# HeaderB.net
KiCad netlist of a schematic drawn in Altium Designer
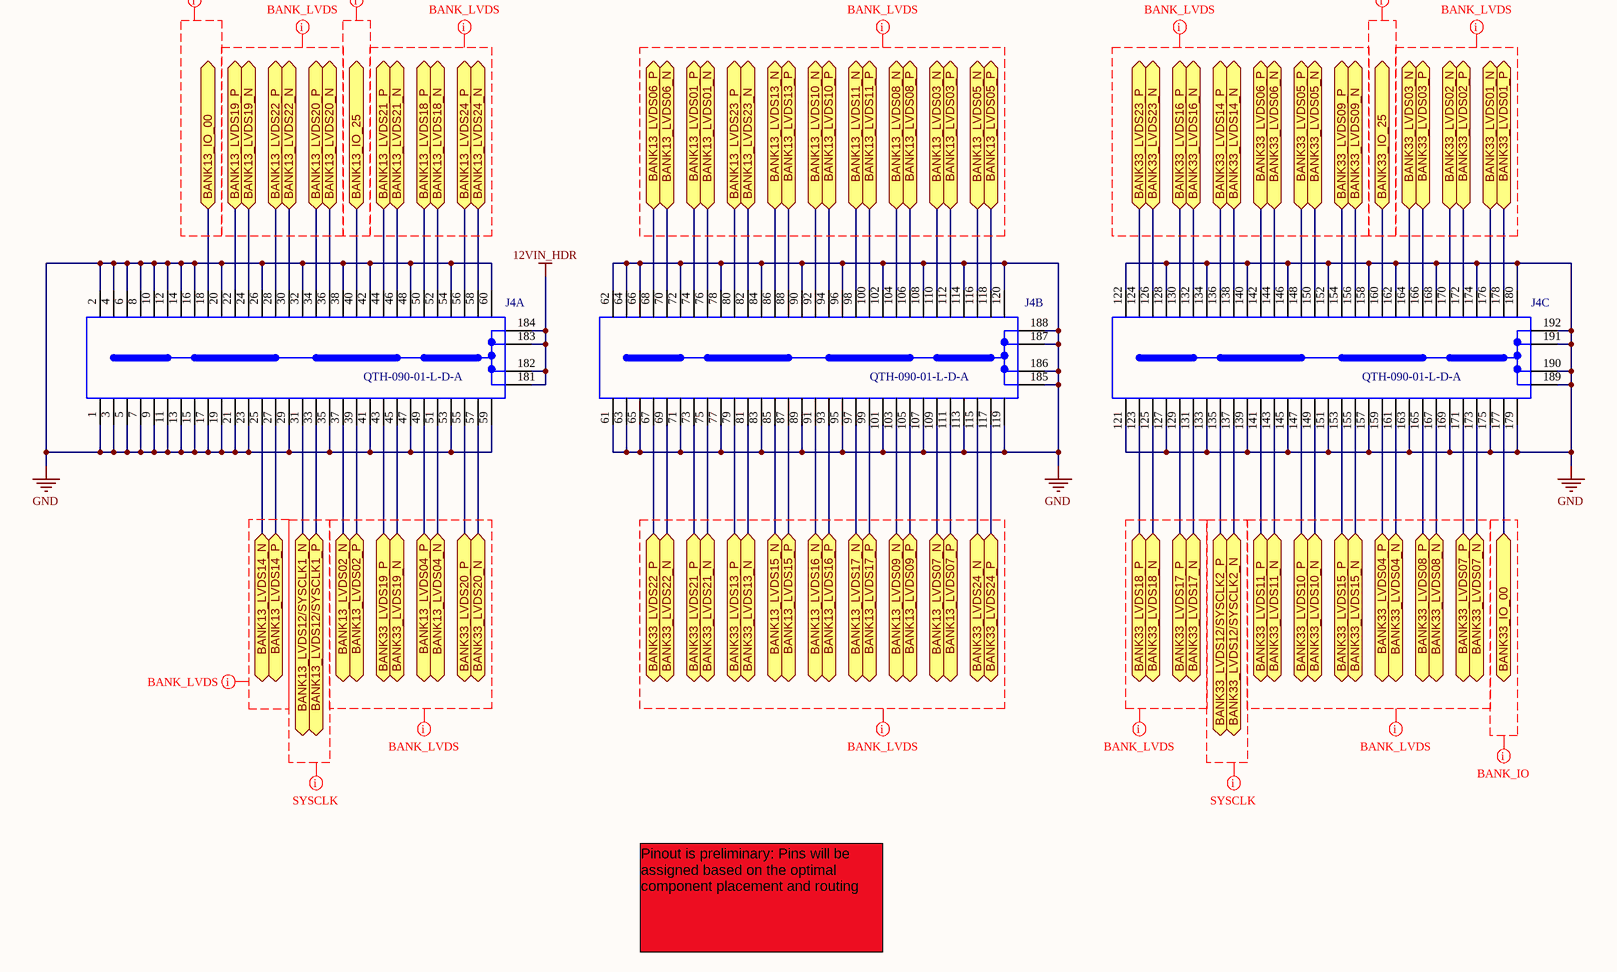
[diagram p0: HeaderB.SchDoc]

(export (version "E")
  (design (tool "Eeschema 10.0.6"))
  (components
    (comp (ref "J4")
      (value "QTH-090-01-L-D-A")
      (footprint "QTH-090-01-L-D-A")
      (description "Connector Header HS .5mm 180 pin DL AU")
      (libsource (lib "parts") (part "QTH-090-01-L-D-A"))
    )
  )
  (nets
    (net (code "1") (name "/BANK13_IO_00") (class "Default")
      (node (ref "J4") (pin "18") (pinfunction "18_18") (pintype "passive"))
    )
    (net (code "2") (name "/BANK13_IO_25") (class "Default")
      (node (ref "J4") (pin "40") (pinfunction "40_40") (pintype "passive"))
    )
    (net (code "3") (name "/BANK13_LVDS01_N") (class "Default")
      (node (ref "J4") (pin "76") (pinfunction "76_76") (pintype "passive"))
    )
    (net (code "4") (name "/BANK13_LVDS01_P") (class "Default")
      (node (ref "J4") (pin "74") (pinfunction "74_74") (pintype "passive"))
    )
    (net (code "5") (name "/BANK13_LVDS02_N") (class "Default")
      (node (ref "J4") (pin "37") (pinfunction "37_37") (pintype "passive"))
    )
    (net (code "6") (name "/BANK13_LVDS02_P") (class "Default")
      (node (ref "J4") (pin "39") (pinfunction "39_39") (pintype "passive"))
    )
    (net (code "7") (name "/BANK13_LVDS03_N") (class "Default")
      (node (ref "J4") (pin "110") (pinfunction "110_110") (pintype "passive"))
    )
    (net (code "8") (name "/BANK13_LVDS03_P") (class "Default")
      (node (ref "J4") (pin "112") (pinfunction "112_112") (pintype "passive"))
    )
    (net (code "9") (name "/BANK13_LVDS04_N") (class "Default")
      (node (ref "J4") (pin "51") (pinfunction "51_51") (pintype "passive"))
    )
    (net (code "10") (name "/BANK13_LVDS04_P") (class "Default")
      (node (ref "J4") (pin "49") (pinfunction "49_49") (pintype "passive"))
    )
    (net (code "11") (name "/BANK13_LVDS05_N") (class "Default")
      (node (ref "J4") (pin "116") (pinfunction "116_116") (pintype "passive"))
    )
    (net (code "12") (name "/BANK13_LVDS05_P") (class "Default")
      (node (ref "J4") (pin "118") (pinfunction "118_118") (pintype "passive"))
    )
    (net (code "13") (name "/BANK13_LVDS06_N") (class "Default")
      (node (ref "J4") (pin "70") (pinfunction "70_70") (pintype "passive"))
    )
    (net (code "14") (name "/BANK13_LVDS06_P") (class "Default")
      (node (ref "J4") (pin "68") (pinfunction "68_68") (pintype "passive"))
    )
    (net (code "15") (name "/BANK13_LVDS07_N") (class "Default")
      (node (ref "J4") (pin "109") (pinfunction "109_109") (pintype "passive"))
    )
    (net (code "16") (name "/BANK13_LVDS07_P") (class "Default")
      (node (ref "J4") (pin "111") (pinfunction "111_111") (pintype "passive"))
    )
    (net (code "17") (name "/BANK13_LVDS08_N") (class "Default")
      (node (ref "J4") (pin "104") (pinfunction "104_104") (pintype "passive"))
    )
    (net (code "18") (name "/BANK13_LVDS08_P") (class "Default")
      (node (ref "J4") (pin "106") (pinfunction "106_106") (pintype "passive"))
    )
    (net (code "19") (name "/BANK13_LVDS09_N") (class "Default")
      (node (ref "J4") (pin "103") (pinfunction "103_103") (pintype "passive"))
    )
    (net (code "20") (name "/BANK13_LVDS09_P") (class "Default")
      (node (ref "J4") (pin "105") (pinfunction "105_105") (pintype "passive"))
    )
    (net (code "21") (name "/BANK13_LVDS10_N") (class "Default")
      (node (ref "J4") (pin "92") (pinfunction "92_92") (pintype "passive"))
    )
    (net (code "22") (name "/BANK13_LVDS10_P") (class "Default")
      (node (ref "J4") (pin "94") (pinfunction "94_94") (pintype "passive"))
    )
    (net (code "23") (name "/BANK13_LVDS11_N") (class "Default")
      (node (ref "J4") (pin "98") (pinfunction "98_98") (pintype "passive"))
    )
    (net (code "24") (name "/BANK13_LVDS11_P") (class "Default")
      (node (ref "J4") (pin "100") (pinfunction "100_100") (pintype "passive"))
    )
    (net (code "25") (name "/BANK13_LVDS12{slash}SYSCLK1_N") (class "Default")
      (node (ref "J4") (pin "31") (pinfunction "31_31") (pintype "passive"))
    )
    (net (code "26") (name "/BANK13_LVDS12{slash}SYSCLK1_P") (class "Default")
      (node (ref "J4") (pin "33") (pinfunction "33_33") (pintype "passive"))
    )
    (net (code "27") (name "/BANK13_LVDS13_N") (class "Default")
      (node (ref "J4") (pin "86") (pinfunction "86_86") (pintype "passive"))
    )
    (net (code "28") (name "/BANK13_LVDS13_P") (class "Default")
      (node (ref "J4") (pin "88") (pinfunction "88_88") (pintype "passive"))
    )
    (net (code "29") (name "/BANK13_LVDS14_N") (class "Default")
      (node (ref "J4") (pin "25") (pinfunction "25_25") (pintype "passive"))
    )
    (net (code "30") (name "/BANK13_LVDS14_P") (class "Default")
      (node (ref "J4") (pin "27") (pinfunction "27_27") (pintype "passive"))
    )
    (net (code "31") (name "/BANK13_LVDS15_N") (class "Default")
      (node (ref "J4") (pin "85") (pinfunction "85_85") (pintype "passive"))
    )
    (net (code "32") (name "/BANK13_LVDS15_P") (class "Default")
      (node (ref "J4") (pin "87") (pinfunction "87_87") (pintype "passive"))
    )
    (net (code "33") (name "/BANK13_LVDS16_N") (class "Default")
      (node (ref "J4") (pin "91") (pinfunction "91_91") (pintype "passive"))
    )
    (net (code "34") (name "/BANK13_LVDS16_P") (class "Default")
      (node (ref "J4") (pin "93") (pinfunction "93_93") (pintype "passive"))
    )
    (net (code "35") (name "/BANK13_LVDS17_N") (class "Default")
      (node (ref "J4") (pin "97") (pinfunction "97_97") (pintype "passive"))
    )
    (net (code "36") (name "/BANK13_LVDS17_P") (class "Default")
      (node (ref "J4") (pin "99") (pinfunction "99_99") (pintype "passive"))
    )
    (net (code "37") (name "/BANK13_LVDS18_N") (class "Default")
      (node (ref "J4") (pin "52") (pinfunction "52_52") (pintype "passive"))
    )
    (net (code "38") (name "/BANK13_LVDS18_P") (class "Default")
      (node (ref "J4") (pin "50") (pinfunction "50_50") (pintype "passive"))
    )
    (net (code "39") (name "/BANK13_LVDS19_N") (class "Default")
      (node (ref "J4") (pin "24") (pinfunction "24_24") (pintype "passive"))
    )
    (net (code "40") (name "/BANK13_LVDS19_P") (class "Default")
      (node (ref "J4") (pin "22") (pinfunction "22_22") (pintype "passive"))
    )
    (net (code "41") (name "/BANK13_LVDS20_N") (class "Default")
      (node (ref "J4") (pin "36") (pinfunction "36_36") (pintype "passive"))
    )
    (net (code "42") (name "/BANK13_LVDS20_P") (class "Default")
      (node (ref "J4") (pin "34") (pinfunction "34_34") (pintype "passive"))
    )
    (net (code "43") (name "/BANK13_LVDS21_N") (class "Default")
      (node (ref "J4") (pin "46") (pinfunction "46_46") (pintype "passive"))
    )
    (net (code "44") (name "/BANK13_LVDS21_P") (class "Default")
      (node (ref "J4") (pin "44") (pinfunction "44_44") (pintype "passive"))
    )
    (net (code "45") (name "/BANK13_LVDS22_N") (class "Default")
      (node (ref "J4") (pin "30") (pinfunction "30_30") (pintype "passive"))
    )
    (net (code "46") (name "/BANK13_LVDS22_P") (class "Default")
      (node (ref "J4") (pin "28") (pinfunction "28_28") (pintype "passive"))
    )
    (net (code "47") (name "/BANK13_LVDS23_N") (class "Default")
      (node (ref "J4") (pin "82") (pinfunction "82_82") (pintype "passive"))
    )
    (net (code "48") (name "/BANK13_LVDS23_P") (class "Default")
      (node (ref "J4") (pin "80") (pinfunction "80_80") (pintype "passive"))
    )
    (net (code "49") (name "/BANK13_LVDS24_N") (class "Default")
      (node (ref "J4") (pin "58") (pinfunction "58_58") (pintype "passive"))
    )
    (net (code "50") (name "/BANK13_LVDS24_P") (class "Default")
      (node (ref "J4") (pin "56") (pinfunction "56_56") (pintype "passive"))
    )
    (net (code "51") (name "/BANK33_IO_00") (class "Default")
      (node (ref "J4") (pin "177") (pinfunction "177_177") (pintype "passive"))
    )
    (net (code "52") (name "/BANK33_IO_25") (class "Default")
      (node (ref "J4") (pin "160") (pinfunction "160_160") (pintype "passive"))
    )
    (net (code "53") (name "/BANK33_LVDS01_N") (class "Default")
      (node (ref "J4") (pin "176") (pinfunction "176_176") (pintype "passive"))
    )
    (net (code "54") (name "/BANK33_LVDS01_P") (class "Default")
      (node (ref "J4") (pin "178") (pinfunction "178_178") (pintype "passive"))
    )
    (net (code "55") (name "/BANK33_LVDS02_N") (class "Default")
      (node (ref "J4") (pin "170") (pinfunction "170_170") (pintype "passive"))
    )
    (net (code "56") (name "/BANK33_LVDS02_P") (class "Default")
      (node (ref "J4") (pin "172") (pinfunction "172_172") (pintype "passive"))
    )
    (net (code "57") (name "/BANK33_LVDS03_N") (class "Default")
      (node (ref "J4") (pin "164") (pinfunction "164_164") (pintype "passive"))
    )
    (net (code "58") (name "/BANK33_LVDS03_P") (class "Default")
      (node (ref "J4") (pin "166") (pinfunction "166_166") (pintype "passive"))
    )
    (net (code "59") (name "/BANK33_LVDS04_N") (class "Default")
      (node (ref "J4") (pin "161") (pinfunction "161_161") (pintype "passive"))
    )
    (net (code "60") (name "/BANK33_LVDS04_P") (class "Default")
      (node (ref "J4") (pin "159") (pinfunction "159_159") (pintype "passive"))
    )
    (net (code "61") (name "/BANK33_LVDS05_N") (class "Default")
      (node (ref "J4") (pin "150") (pinfunction "150_150") (pintype "passive"))
    )
    (net (code "62") (name "/BANK33_LVDS05_P") (class "Default")
      (node (ref "J4") (pin "148") (pinfunction "148_148") (pintype "passive"))
    )
    (net (code "63") (name "/BANK33_LVDS06_N") (class "Default")
      (node (ref "J4") (pin "144") (pinfunction "144_144") (pintype "passive"))
    )
    (net (code "64") (name "/BANK33_LVDS06_P") (class "Default")
      (node (ref "J4") (pin "142") (pinfunction "142_142") (pintype "passive"))
    )
    (net (code "65") (name "/BANK33_LVDS07_N") (class "Default")
      (node (ref "J4") (pin "173") (pinfunction "173_173") (pintype "passive"))
    )
    (net (code "66") (name "/BANK33_LVDS07_P") (class "Default")
      (node (ref "J4") (pin "171") (pinfunction "171_171") (pintype "passive"))
    )
    (net (code "67") (name "/BANK33_LVDS08_N") (class "Default")
      (node (ref "J4") (pin "167") (pinfunction "167_167") (pintype "passive"))
    )
    (net (code "68") (name "/BANK33_LVDS08_P") (class "Default")
      (node (ref "J4") (pin "165") (pinfunction "165_165") (pintype "passive"))
    )
    (net (code "69") (name "/BANK33_LVDS09_N") (class "Default")
      (node (ref "J4") (pin "156") (pinfunction "156_156") (pintype "passive"))
    )
    (net (code "70") (name "/BANK33_LVDS09_P") (class "Default")
      (node (ref "J4") (pin "154") (pinfunction "154_154") (pintype "passive"))
    )
    (net (code "71") (name "/BANK33_LVDS10_N") (class "Default")
      (node (ref "J4") (pin "149") (pinfunction "149_149") (pintype "passive"))
    )
    (net (code "72") (name "/BANK33_LVDS10_P") (class "Default")
      (node (ref "J4") (pin "147") (pinfunction "147_147") (pintype "passive"))
    )
    (net (code "73") (name "/BANK33_LVDS11_N") (class "Default")
      (node (ref "J4") (pin "143") (pinfunction "143_143") (pintype "passive"))
    )
    (net (code "74") (name "/BANK33_LVDS11_P") (class "Default")
      (node (ref "J4") (pin "141") (pinfunction "141_141") (pintype "passive"))
    )
    (net (code "75") (name "/BANK33_LVDS12{slash}SYSCLK2_N") (class "Default")
      (node (ref "J4") (pin "137") (pinfunction "137_137") (pintype "passive"))
    )
    (net (code "76") (name "/BANK33_LVDS12{slash}SYSCLK2_P") (class "Default")
      (node (ref "J4") (pin "135") (pinfunction "135_135") (pintype "passive"))
    )
    (net (code "77") (name "/BANK33_LVDS13_N") (class "Default")
      (node (ref "J4") (pin "81") (pinfunction "81_81") (pintype "passive"))
    )
    (net (code "78") (name "/BANK33_LVDS13_P") (class "Default")
      (node (ref "J4") (pin "79") (pinfunction "79_79") (pintype "passive"))
    )
    (net (code "79") (name "/BANK33_LVDS14_N") (class "Default")
      (node (ref "J4") (pin "138") (pinfunction "138_138") (pintype "passive"))
    )
    (net (code "80") (name "/BANK33_LVDS14_P") (class "Default")
      (node (ref "J4") (pin "136") (pinfunction "136_136") (pintype "passive"))
    )
    (net (code "81") (name "/BANK33_LVDS15_N") (class "Default")
      (node (ref "J4") (pin "155") (pinfunction "155_155") (pintype "passive"))
    )
    (net (code "82") (name "/BANK33_LVDS15_P") (class "Default")
      (node (ref "J4") (pin "153") (pinfunction "153_153") (pintype "passive"))
    )
    (net (code "83") (name "/BANK33_LVDS16_N") (class "Default")
      (node (ref "J4") (pin "132") (pinfunction "132_132") (pintype "passive"))
    )
    (net (code "84") (name "/BANK33_LVDS16_P") (class "Default")
      (node (ref "J4") (pin "130") (pinfunction "130_130") (pintype "passive"))
    )
    (net (code "85") (name "/BANK33_LVDS17_N") (class "Default")
      (node (ref "J4") (pin "131") (pinfunction "131_131") (pintype "passive"))
    )
    (net (code "86") (name "/BANK33_LVDS17_P") (class "Default")
      (node (ref "J4") (pin "129") (pinfunction "129_129") (pintype "passive"))
    )
    (net (code "87") (name "/BANK33_LVDS18_N") (class "Default")
      (node (ref "J4") (pin "125") (pinfunction "125_125") (pintype "passive"))
    )
    (net (code "88") (name "/BANK33_LVDS18_P") (class "Default")
      (node (ref "J4") (pin "123") (pinfunction "123_123") (pintype "passive"))
    )
    (net (code "89") (name "/BANK33_LVDS19_N") (class "Default")
      (node (ref "J4") (pin "45") (pinfunction "45_45") (pintype "passive"))
    )
    (net (code "90") (name "/BANK33_LVDS19_P") (class "Default")
      (node (ref "J4") (pin "43") (pinfunction "43_43") (pintype "passive"))
    )
    (net (code "91") (name "/BANK33_LVDS20_N") (class "Default")
      (node (ref "J4") (pin "57") (pinfunction "57_57") (pintype "passive"))
    )
    (net (code "92") (name "/BANK33_LVDS20_P") (class "Default")
      (node (ref "J4") (pin "55") (pinfunction "55_55") (pintype "passive"))
    )
    (net (code "93") (name "/BANK33_LVDS21_N") (class "Default")
      (node (ref "J4") (pin "75") (pinfunction "75_75") (pintype "passive"))
    )
    (net (code "94") (name "/BANK33_LVDS21_P") (class "Default")
      (node (ref "J4") (pin "73") (pinfunction "73_73") (pintype "passive"))
    )
    (net (code "95") (name "/BANK33_LVDS22_N") (class "Default")
      (node (ref "J4") (pin "69") (pinfunction "69_69") (pintype "passive"))
    )
    (net (code "96") (name "/BANK33_LVDS22_P") (class "Default")
      (node (ref "J4") (pin "67") (pinfunction "67_67") (pintype "passive"))
    )
    (net (code "97") (name "/BANK33_LVDS23_N") (class "Default")
      (node (ref "J4") (pin "126") (pinfunction "126_126") (pintype "passive"))
    )
    (net (code "98") (name "/BANK33_LVDS23_P") (class "Default")
      (node (ref "J4") (pin "124") (pinfunction "124_124") (pintype "passive"))
    )
    (net (code "99") (name "/BANK33_LVDS24_N") (class "Default")
      (node (ref "J4") (pin "115") (pinfunction "115_115") (pintype "passive"))
    )
    (net (code "100") (name "/BANK33_LVDS24_P") (class "Default")
      (node (ref "J4") (pin "117") (pinfunction "117_117") (pintype "passive"))
    )
    (net (code "101") (name "12VIN_HDR") (class "Default")
      (node (ref "J4") (pin "181") (pinfunction "181_181") (pintype "passive"))
      (node (ref "J4") (pin "182") (pinfunction "182_182") (pintype "passive"))
      (node (ref "J4") (pin "183") (pinfunction "183_183") (pintype "passive"))
      (node (ref "J4") (pin "184") (pinfunction "184_184") (pintype "passive"))
    )
    (net (code "102") (name "GND") (class "Default")
      (node (ref "J4") (pin "1") (pinfunction "1_1") (pintype "passive"))
      (node (ref "J4") (pin "10") (pinfunction "10_10") (pintype "passive"))
      (node (ref "J4") (pin "101") (pinfunction "101_101") (pintype "passive"))
      (node (ref "J4") (pin "102") (pinfunction "102_102") (pintype "passive"))
      (node (ref "J4") (pin "107") (pinfunction "107_107") (pintype "passive"))
      (node (ref "J4") (pin "108") (pinfunction "108_108") (pintype "passive"))
      (node (ref "J4") (pin "11") (pinfunction "11_11") (pintype "passive"))
      (node (ref "J4") (pin "113") (pinfunction "113_113") (pintype "passive"))
      (node (ref "J4") (pin "114") (pinfunction "114_114") (pintype "passive"))
      (node (ref "J4") (pin "119") (pinfunction "119_119") (pintype "passive"))
      (node (ref "J4") (pin "12") (pinfunction "12_12") (pintype "passive"))
      (node (ref "J4") (pin "120") (pinfunction "120_120") (pintype "passive"))
      (node (ref "J4") (pin "121") (pinfunction "121_121") (pintype "passive"))
      (node (ref "J4") (pin "122") (pinfunction "122_122") (pintype "passive"))
      (node (ref "J4") (pin "127") (pinfunction "127_127") (pintype "passive"))
      (node (ref "J4") (pin "128") (pinfunction "128_128") (pintype "passive"))
      (node (ref "J4") (pin "13") (pinfunction "13_13") (pintype "passive"))
      (node (ref "J4") (pin "133") (pinfunction "133_133") (pintype "passive"))
      (node (ref "J4") (pin "134") (pinfunction "134_134") (pintype "passive"))
      (node (ref "J4") (pin "139") (pinfunction "139_139") (pintype "passive"))
      (node (ref "J4") (pin "14") (pinfunction "14_14") (pintype "passive"))
      (node (ref "J4") (pin "140") (pinfunction "140_140") (pintype "passive"))
      (node (ref "J4") (pin "145") (pinfunction "145_145") (pintype "passive"))
      (node (ref "J4") (pin "146") (pinfunction "146_146") (pintype "passive"))
      (node (ref "J4") (pin "15") (pinfunction "15_15") (pintype "passive"))
      (node (ref "J4") (pin "151") (pinfunction "151_151") (pintype "passive"))
      (node (ref "J4") (pin "152") (pinfunction "152_152") (pintype "passive"))
      (node (ref "J4") (pin "157") (pinfunction "157_157") (pintype "passive"))
      (node (ref "J4") (pin "158") (pinfunction "158_158") (pintype "passive"))
      (node (ref "J4") (pin "16") (pinfunction "16_16") (pintype "passive"))
      (node (ref "J4") (pin "162") (pinfunction "162_162") (pintype "passive"))
      (node (ref "J4") (pin "163") (pinfunction "163_163") (pintype "passive"))
      (node (ref "J4") (pin "168") (pinfunction "168_168") (pintype "passive"))
      (node (ref "J4") (pin "169") (pinfunction "169_169") (pintype "passive"))
      (node (ref "J4") (pin "17") (pinfunction "17_17") (pintype "passive"))
      (node (ref "J4") (pin "174") (pinfunction "174_174") (pintype "passive"))
      (node (ref "J4") (pin "175") (pinfunction "175_175") (pintype "passive"))
      (node (ref "J4") (pin "179") (pinfunction "179_179") (pintype "passive"))
      (node (ref "J4") (pin "180") (pinfunction "180_180") (pintype "passive"))
      (node (ref "J4") (pin "185") (pinfunction "185_185") (pintype "passive"))
      (node (ref "J4") (pin "186") (pinfunction "186_186") (pintype "passive"))
      (node (ref "J4") (pin "187") (pinfunction "187_187") (pintype "passive"))
      (node (ref "J4") (pin "188") (pinfunction "188_188") (pintype "passive"))
      (node (ref "J4") (pin "189") (pinfunction "189_189") (pintype "passive"))
      (node (ref "J4") (pin "19") (pinfunction "19_19") (pintype "passive"))
      (node (ref "J4") (pin "190") (pinfunction "190_190") (pintype "passive"))
      (node (ref "J4") (pin "191") (pinfunction "191_191") (pintype "passive"))
      (node (ref "J4") (pin "192") (pinfunction "192_192") (pintype "passive"))
      (node (ref "J4") (pin "2") (pinfunction "2_2") (pintype "passive"))
      (node (ref "J4") (pin "20") (pinfunction "20_20") (pintype "passive"))
      (node (ref "J4") (pin "21") (pinfunction "21_21") (pintype "passive"))
      (node (ref "J4") (pin "23") (pinfunction "23_23") (pintype "passive"))
      (node (ref "J4") (pin "26") (pinfunction "26_26") (pintype "passive"))
      (node (ref "J4") (pin "29") (pinfunction "29_29") (pintype "passive"))
      (node (ref "J4") (pin "3") (pinfunction "3_3") (pintype "passive"))
      (node (ref "J4") (pin "32") (pinfunction "32_32") (pintype "passive"))
      (node (ref "J4") (pin "35") (pinfunction "35_35") (pintype "passive"))
      (node (ref "J4") (pin "38") (pinfunction "38_38") (pintype "passive"))
      (node (ref "J4") (pin "4") (pinfunction "4_4") (pintype "passive"))
      (node (ref "J4") (pin "41") (pinfunction "41_41") (pintype "passive"))
      (node (ref "J4") (pin "42") (pinfunction "42_42") (pintype "passive"))
      (node (ref "J4") (pin "47") (pinfunction "47_47") (pintype "passive"))
      (node (ref "J4") (pin "48") (pinfunction "48_48") (pintype "passive"))
      (node (ref "J4") (pin "5") (pinfunction "5_5") (pintype "passive"))
      (node (ref "J4") (pin "53") (pinfunction "53_53") (pintype "passive"))
      (node (ref "J4") (pin "54") (pinfunction "54_54") (pintype "passive"))
      (node (ref "J4") (pin "59") (pinfunction "59_59") (pintype "passive"))
      (node (ref "J4") (pin "6") (pinfunction "6_6") (pintype "passive"))
      (node (ref "J4") (pin "60") (pinfunction "60_60") (pintype "passive"))
      (node (ref "J4") (pin "61") (pinfunction "61_61") (pintype "passive"))
      (node (ref "J4") (pin "62") (pinfunction "62_62") (pintype "passive"))
      (node (ref "J4") (pin "63") (pinfunction "63_63") (pintype "passive"))
      (node (ref "J4") (pin "64") (pinfunction "64_64") (pintype "passive"))
      (node (ref "J4") (pin "65") (pinfunction "65_65") (pintype "passive"))
      (node (ref "J4") (pin "66") (pinfunction "66_66") (pintype "passive"))
      (node (ref "J4") (pin "7") (pinfunction "7_7") (pintype "passive"))
      (node (ref "J4") (pin "71") (pinfunction "71_71") (pintype "passive"))
      (node (ref "J4") (pin "72") (pinfunction "72_72") (pintype "passive"))
      (node (ref "J4") (pin "77") (pinfunction "77_77") (pintype "passive"))
      (node (ref "J4") (pin "78") (pinfunction "78_78") (pintype "passive"))
      (node (ref "J4") (pin "8") (pinfunction "8_8") (pintype "passive"))
      (node (ref "J4") (pin "83") (pinfunction "83_83") (pintype "passive"))
      (node (ref "J4") (pin "84") (pinfunction "84_84") (pintype "passive"))
      (node (ref "J4") (pin "89") (pinfunction "89_89") (pintype "passive"))
      (node (ref "J4") (pin "9") (pinfunction "9_9") (pintype "passive"))
      (node (ref "J4") (pin "90") (pinfunction "90_90") (pintype "passive"))
      (node (ref "J4") (pin "95") (pinfunction "95_95") (pintype "passive"))
      (node (ref "J4") (pin "96") (pinfunction "96_96") (pintype "passive"))
    )
  )
)
